# BIAS.net
KiCad netlist of a schematic drawn in Altium Designer
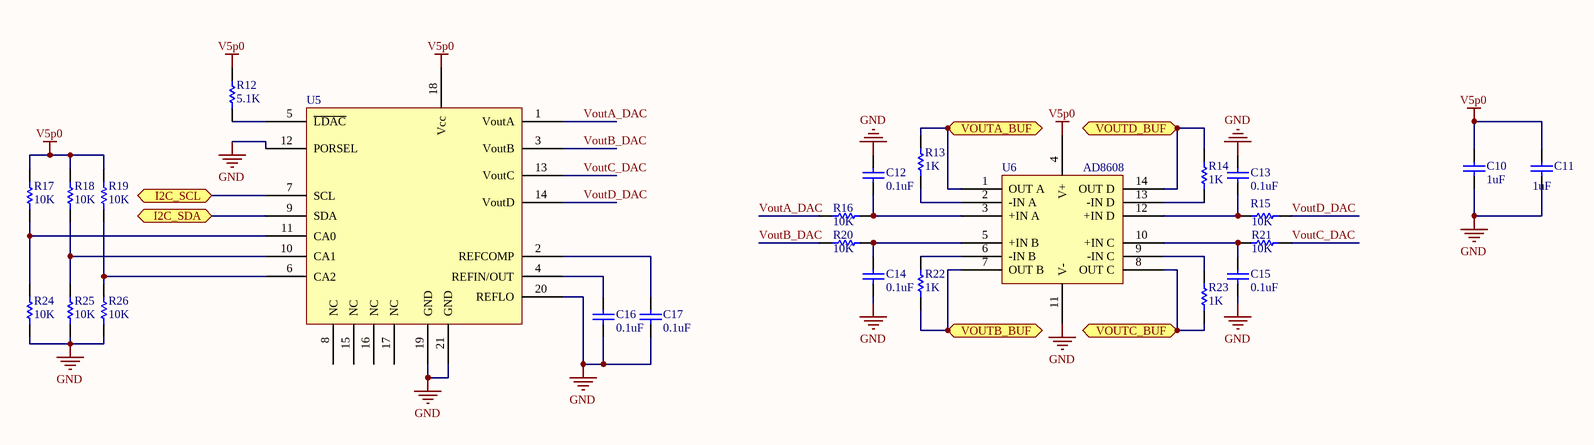
[diagram p0: BIAS.SchDoc]

(export (version "E")
  (design (tool "Eeschema 10.0.6"))
  (components
    (comp (ref "C10")
      (value "1uF")
      (footprint "CAPC01005(0402)22_N")
      (fields (field (name "Comment") "CAP, 0402, 1uF"))
      (libsource (lib "Components") (part "CAP, 0402, 1uF"))
    )
    (comp (ref "C11")
      (value "1uF")
      (footprint "CAPC01005(0402)22_N")
      (fields (field (name "Comment") "CAP, 0402, 1uF"))
      (libsource (lib "Components") (part "CAP, 0402, 1uF"))
    )
    (comp (ref "C12")
      (value "0.1uF")
      (footprint "CAPC01005(0402)22_N")
      (fields (field (name "Comment") "CAP, 0402, 0.1uF"))
      (libsource (lib "Components") (part "CAP, 0402, 0.1uF"))
    )
    (comp (ref "C13")
      (value "0.1uF")
      (footprint "CAPC01005(0402)22_N")
      (fields (field (name "Comment") "CAP, 0402, 0.1uF"))
      (libsource (lib "Components") (part "CAP, 0402, 0.1uF"))
    )
    (comp (ref "C14")
      (value "0.1uF")
      (footprint "CAPC01005(0402)22_N")
      (fields (field (name "Comment") "CAP, 0402, 0.1uF"))
      (libsource (lib "Components") (part "CAP, 0402, 0.1uF"))
    )
    (comp (ref "C15")
      (value "0.1uF")
      (footprint "CAPC01005(0402)22_N")
      (fields (field (name "Comment") "CAP, 0402, 0.1uF"))
      (libsource (lib "Components") (part "CAP, 0402, 0.1uF"))
    )
    (comp (ref "C16")
      (value "0.1uF")
      (footprint "CAPC01005(0402)22_N")
      (fields (field (name "Comment") "CAP, 0402, 0.1uF"))
      (libsource (lib "Components") (part "CAP, 0402, 0.1uF"))
    )
    (comp (ref "C17")
      (value "0.1uF")
      (footprint "CAPC01005(0402)22_N")
      (fields (field (name "Comment") "CAP, 0402, 0.1uF"))
      (libsource (lib "Components") (part "CAP, 0402, 0.1uF"))
    )
    (comp (ref "R12")
      (value "5.1K")
      (footprint "RES, 0603")
      (description "Resistor, 0603, 1/10W, 5.1K ohm")
      (fields
        (field (name "MANUFACTURER") "Panasonic Electronic Components")
        (field (name "MANUFACTURER PART NUMBER") "ERJ-3EKF5101V")
      )
      (libsource (lib "Resistors0603") (part "RES_0603_5.1K"))
    )
    (comp (ref "R13")
      (value "1K")
      (footprint "RES, 0603")
      (description "Resistor, 0603, 1/10W, 1K ohm")
      (fields
        (field (name "MANUFACTURER") "Panasonic Electronic Components")
        (field (name "MANUFACTURER PART NUMBER") "ERJ-3EKF1001V")
      )
      (libsource (lib "Resistors0603") (part "RES_0603_1K"))
    )
    (comp (ref "R14")
      (value "1K")
      (footprint "RES, 0603")
      (description "Resistor, 0603, 1/10W, 1K ohm")
      (fields
        (field (name "MANUFACTURER") "Panasonic Electronic Components")
        (field (name "MANUFACTURER PART NUMBER") "ERJ-3EKF1001V")
      )
      (libsource (lib "Resistors0603") (part "RES_0603_1K"))
    )
    (comp (ref "R15")
      (value "10K")
      (footprint "RES, 0603")
      (description "Resistor, 0603, 1/10W, 10K ohm")
      (fields
        (field (name "MANUFACTURER") "Panasonic Electronic Components")
        (field (name "MANUFACTURER PART NUMBER") "ERJ-3EKF1002V")
      )
      (libsource (lib "Resistors0603") (part "RES_0603_10K"))
    )
    (comp (ref "R16")
      (value "10K")
      (footprint "RES, 0603")
      (description "Resistor, 0603, 1/10W, 10K ohm")
      (fields
        (field (name "MANUFACTURER") "Panasonic Electronic Components")
        (field (name "MANUFACTURER PART NUMBER") "ERJ-3EKF1002V")
      )
      (libsource (lib "Resistors0603") (part "RES_0603_10K"))
    )
    (comp (ref "R17")
      (value "10K")
      (footprint "RES, 0603")
      (description "Resistor, 0603, 1/10W, 10K ohm")
      (fields
        (field (name "MANUFACTURER") "Panasonic Electronic Components")
        (field (name "MANUFACTURER PART NUMBER") "ERJ-3EKF1002V")
      )
      (libsource (lib "Resistors0603") (part "RES_0603_10K"))
    )
    (comp (ref "R18")
      (value "10K")
      (footprint "RES, 0603")
      (description "Resistor, 0603, 1/10W, 10K ohm")
      (fields
        (field (name "MANUFACTURER") "Panasonic Electronic Components")
        (field (name "MANUFACTURER PART NUMBER") "ERJ-3EKF1002V")
      )
      (libsource (lib "Resistors0603") (part "RES_0603_10K"))
    )
    (comp (ref "R19")
      (value "10K")
      (footprint "RES, 0603")
      (description "Resistor, 0603, 1/10W, 10K ohm")
      (fields
        (field (name "MANUFACTURER") "Panasonic Electronic Components")
        (field (name "MANUFACTURER PART NUMBER") "ERJ-3EKF1002V")
      )
      (libsource (lib "Resistors0603") (part "RES_0603_10K"))
    )
    (comp (ref "R20")
      (value "10K")
      (footprint "RES, 0603")
      (description "Resistor, 0603, 1/10W, 10K ohm")
      (fields
        (field (name "MANUFACTURER") "Panasonic Electronic Components")
        (field (name "MANUFACTURER PART NUMBER") "ERJ-3EKF1002V")
      )
      (libsource (lib "Resistors0603") (part "RES_0603_10K"))
    )
    (comp (ref "R21")
      (value "10K")
      (footprint "RES, 0603")
      (description "Resistor, 0603, 1/10W, 10K ohm")
      (fields
        (field (name "MANUFACTURER") "Panasonic Electronic Components")
        (field (name "MANUFACTURER PART NUMBER") "ERJ-3EKF1002V")
      )
      (libsource (lib "Resistors0603") (part "RES_0603_10K"))
    )
    (comp (ref "R22")
      (value "1K")
      (footprint "RES, 0603")
      (description "Resistor, 0603, 1/10W, 1K ohm")
      (fields
        (field (name "MANUFACTURER") "Panasonic Electronic Components")
        (field (name "MANUFACTURER PART NUMBER") "ERJ-3EKF1001V")
      )
      (libsource (lib "Resistors0603") (part "RES_0603_1K"))
    )
    (comp (ref "R23")
      (value "1K")
      (footprint "RES, 0603")
      (description "Resistor, 0603, 1/10W, 1K ohm")
      (fields
        (field (name "MANUFACTURER") "Panasonic Electronic Components")
        (field (name "MANUFACTURER PART NUMBER") "ERJ-3EKF1001V")
      )
      (libsource (lib "Resistors0603") (part "RES_0603_1K"))
    )
    (comp (ref "R24")
      (value "10K")
      (footprint "RES, 0603")
      (description "Resistor, 0603, 1/10W, 10K ohm")
      (fields
        (field (name "MANUFACTURER") "Panasonic Electronic Components")
        (field (name "MANUFACTURER PART NUMBER") "ERJ-3EKF1002V")
      )
      (libsource (lib "Resistors0603") (part "RES_0603_10K"))
    )
    (comp (ref "R25")
      (value "10K")
      (footprint "RES, 0603")
      (description "Resistor, 0603, 1/10W, 10K ohm")
      (fields
        (field (name "MANUFACTURER") "Panasonic Electronic Components")
        (field (name "MANUFACTURER PART NUMBER") "ERJ-3EKF1002V")
      )
      (libsource (lib "Resistors0603") (part "RES_0603_10K"))
    )
    (comp (ref "R26")
      (value "10K")
      (footprint "RES, 0603")
      (description "Resistor, 0603, 1/10W, 10K ohm")
      (fields
        (field (name "MANUFACTURER") "Panasonic Electronic Components")
        (field (name "MANUFACTURER PART NUMBER") "ERJ-3EKF1002V")
      )
      (libsource (lib "Resistors0603") (part "RES_0603_10K"))
    )
    (comp (ref "U5")
      (value "LTC2655")
      (footprint "QFN50P400X400X70-20N")
      (description "Quad I2C 16-/12-Bit Rail-to-Rail DACs with 10ppm/°C Max Reference")
      (libsource (lib "Components") (part "LTC2655"))
    )
    (comp (ref "U6")
      (value "AD8608")
      (footprint "TSOP65P640X120-14N")
      (description "IC OPAMP GP 10MHZ RRO 14SOIC")
      (fields
        (field (name "MANUFACTURER") "Analog Devices Inc")
        (field (name "MANUFACTURER PART NUMBER") "AD8608ARZ-REEL")
      )
      (libsource (lib "Components") (part "AD8608; Quad Op-Amp"))
    )
  )
  (nets
    (net (code "1") (name "/I2C_SCL") (class "Default")
      (node (ref "U5") (pin "7") (pinfunction "SCL_7") (pintype "passive"))
    )
    (net (code "2") (name "/I2C_SDA") (class "Default")
      (node (ref "U5") (pin "9") (pinfunction "SDA_9") (pintype "passive"))
    )
    (net (code "3") (name "/VOUTA_BUF") (class "Default")
      (node (ref "R13") (pin "2") (pinfunction "2_2") (pintype "passive"))
      (node (ref "U6") (pin "1") (pinfunction "OUT_A_1") (pintype "passive"))
    )
    (net (code "4") (name "/VOUTB_BUF") (class "Default")
      (node (ref "R22") (pin "1") (pinfunction "1_1") (pintype "passive"))
      (node (ref "U6") (pin "7") (pinfunction "OUT_B_7") (pintype "passive"))
    )
    (net (code "5") (name "/VOUTC_BUF") (class "Default")
      (node (ref "R23") (pin "2") (pinfunction "2_2") (pintype "passive"))
      (node (ref "U6") (pin "8") (pinfunction "OUT_C_8") (pintype "passive"))
    )
    (net (code "6") (name "/VOUTD_BUF") (class "Default")
      (node (ref "R14") (pin "1") (pinfunction "1_1") (pintype "passive"))
      (node (ref "U6") (pin "14") (pinfunction "OUT_D_14") (pintype "passive"))
    )
    (net (code "7") (name "/VoutA_DAC") (class "Default")
      (node (ref "R16") (pin "1") (pinfunction "1_1") (pintype "passive"))
      (node (ref "U5") (pin "1") (pinfunction "VoutA_1") (pintype "passive"))
    )
    (net (code "8") (name "/VoutB_DAC") (class "Default")
      (node (ref "R20") (pin "1") (pinfunction "1_1") (pintype "passive"))
      (node (ref "U5") (pin "3") (pinfunction "VoutB_3") (pintype "passive"))
    )
    (net (code "9") (name "/VoutC_DAC") (class "Default")
      (node (ref "R21") (pin "1") (pinfunction "1_1") (pintype "passive"))
      (node (ref "U5") (pin "13") (pinfunction "VoutC_13") (pintype "passive"))
    )
    (net (code "10") (name "/VoutD_DAC") (class "Default")
      (node (ref "R15") (pin "1") (pinfunction "1_1") (pintype "passive"))
      (node (ref "U5") (pin "14") (pinfunction "VoutD_14") (pintype "passive"))
    )
    (net (code "11") (name "GND") (class "Default")
      (node (ref "C10") (pin "1") (pinfunction "1_1") (pintype "passive"))
      (node (ref "C11") (pin "1") (pinfunction "1_1") (pintype "passive"))
      (node (ref "C12") (pin "2") (pinfunction "2_2") (pintype "passive"))
      (node (ref "C13") (pin "1") (pinfunction "1_1") (pintype "passive"))
      (node (ref "C14") (pin "1") (pinfunction "1_1") (pintype "passive"))
      (node (ref "C15") (pin "2") (pinfunction "2_2") (pintype "passive"))
      (node (ref "C16") (pin "1") (pinfunction "1_1") (pintype "passive"))
      (node (ref "C17") (pin "1") (pinfunction "1_1") (pintype "passive"))
      (node (ref "R24") (pin "2") (pinfunction "2_2") (pintype "passive"))
      (node (ref "R25") (pin "2") (pinfunction "2_2") (pintype "passive"))
      (node (ref "R26") (pin "2") (pinfunction "2_2") (pintype "passive"))
      (node (ref "U5") (pin "12") (pinfunction "PORSEL_12") (pintype "passive"))
      (node (ref "U5") (pin "19") (pinfunction "GND_19") (pintype "passive"))
      (node (ref "U5") (pin "20") (pinfunction "REFLO_20") (pintype "passive"))
      (node (ref "U5") (pin "21") (pinfunction "GND_21") (pintype "passive"))
      (node (ref "U6") (pin "11") (pinfunction "V-_11") (pintype "passive"))
    )
    (net (code "12") (name "Net-(U5-CA0)") (class "Default")
      (node (ref "R17") (pin "2") (pinfunction "2_2") (pintype "passive"))
      (node (ref "R24") (pin "1") (pinfunction "1_1") (pintype "passive"))
      (node (ref "U5") (pin "11") (pinfunction "CA0_11") (pintype "passive"))
    )
    (net (code "13") (name "Net-(U5-CA1)") (class "Default")
      (node (ref "R18") (pin "2") (pinfunction "2_2") (pintype "passive"))
      (node (ref "R25") (pin "1") (pinfunction "1_1") (pintype "passive"))
      (node (ref "U5") (pin "10") (pinfunction "CA1_10") (pintype "passive"))
    )
    (net (code "14") (name "Net-(U5-CA2)") (class "Default")
      (node (ref "R19") (pin "2") (pinfunction "2_2") (pintype "passive"))
      (node (ref "R26") (pin "1") (pinfunction "1_1") (pintype "passive"))
      (node (ref "U5") (pin "6") (pinfunction "CA2_6") (pintype "passive"))
    )
    (net (code "15") (name "Net-(U5-REFCOMP)") (class "Default")
      (node (ref "C17") (pin "2") (pinfunction "2_2") (pintype "passive"))
      (node (ref "U5") (pin "2") (pinfunction "REFCOMP_2") (pintype "passive"))
    )
    (net (code "16") (name "Net-(U5-REFIN{slash}OUT)") (class "Default")
      (node (ref "C16") (pin "2") (pinfunction "2_2") (pintype "passive"))
      (node (ref "U5") (pin "4") (pinfunction "REFIN/OUT_4") (pintype "passive"))
    )
    (net (code "17") (name "Net-(U5-~{LDAC})") (class "Default")
      (node (ref "R12") (pin "1") (pinfunction "1_1") (pintype "passive"))
      (node (ref "U5") (pin "5") (pinfunction "~{LDAC}_5") (pintype "passive"))
    )
    (net (code "18") (name "Net-(U6-+IN_A)") (class "Default")
      (node (ref "C12") (pin "1") (pinfunction "1_1") (pintype "passive"))
      (node (ref "R16") (pin "2") (pinfunction "2_2") (pintype "passive"))
      (node (ref "U6") (pin "3") (pinfunction "+IN_A_3") (pintype "passive"))
    )
    (net (code "19") (name "Net-(U6-+IN_B)") (class "Default")
      (node (ref "C14") (pin "2") (pinfunction "2_2") (pintype "passive"))
      (node (ref "R20") (pin "2") (pinfunction "2_2") (pintype "passive"))
      (node (ref "U6") (pin "5") (pinfunction "+IN_B_5") (pintype "passive"))
    )
    (net (code "20") (name "Net-(U6-+IN_C)") (class "Default")
      (node (ref "C15") (pin "1") (pinfunction "1_1") (pintype "passive"))
      (node (ref "R21") (pin "2") (pinfunction "2_2") (pintype "passive"))
      (node (ref "U6") (pin "10") (pinfunction "+IN_C_10") (pintype "passive"))
    )
    (net (code "21") (name "Net-(U6-+IN_D)") (class "Default")
      (node (ref "C13") (pin "2") (pinfunction "2_2") (pintype "passive"))
      (node (ref "R15") (pin "2") (pinfunction "2_2") (pintype "passive"))
      (node (ref "U6") (pin "12") (pinfunction "+IN_D_12") (pintype "passive"))
    )
    (net (code "22") (name "Net-(U6--IN_A)") (class "Default")
      (node (ref "R13") (pin "1") (pinfunction "1_1") (pintype "passive"))
      (node (ref "U6") (pin "2") (pinfunction "-IN_A_2") (pintype "passive"))
    )
    (net (code "23") (name "Net-(U6--IN_B)") (class "Default")
      (node (ref "R22") (pin "2") (pinfunction "2_2") (pintype "passive"))
      (node (ref "U6") (pin "6") (pinfunction "-IN_B_6") (pintype "passive"))
    )
    (net (code "24") (name "Net-(U6--IN_C)") (class "Default")
      (node (ref "R23") (pin "1") (pinfunction "1_1") (pintype "passive"))
      (node (ref "U6") (pin "9") (pinfunction "-IN_C_9") (pintype "passive"))
    )
    (net (code "25") (name "Net-(U6--IN_D)") (class "Default")
      (node (ref "R14") (pin "2") (pinfunction "2_2") (pintype "passive"))
      (node (ref "U6") (pin "13") (pinfunction "-IN_D_13") (pintype "passive"))
    )
    (net (code "26") (name "V5p0") (class "Default")
      (node (ref "C10") (pin "2") (pinfunction "2_2") (pintype "passive"))
      (node (ref "C11") (pin "2") (pinfunction "2_2") (pintype "passive"))
      (node (ref "R12") (pin "2") (pinfunction "2_2") (pintype "passive"))
      (node (ref "R17") (pin "1") (pinfunction "1_1") (pintype "passive"))
      (node (ref "R18") (pin "1") (pinfunction "1_1") (pintype "passive"))
      (node (ref "R19") (pin "1") (pinfunction "1_1") (pintype "passive"))
      (node (ref "U5") (pin "18") (pinfunction "Vcc_18") (pintype "passive"))
      (node (ref "U6") (pin "4") (pinfunction "V+_4") (pintype "passive"))
    )
    (net (code "27") (name "unconnected-(U5-NC-Pad8)") (class "Default")
      (node (ref "U5") (pin "8") (pinfunction "NC_8") (pintype "passive"))
    )
    (net (code "28") (name "unconnected-(U5-NC-Pad15)") (class "Default")
      (node (ref "U5") (pin "15") (pinfunction "NC_15") (pintype "passive"))
    )
    (net (code "29") (name "unconnected-(U5-NC-Pad16)") (class "Default")
      (node (ref "U5") (pin "16") (pinfunction "NC_16") (pintype "passive"))
    )
    (net (code "30") (name "unconnected-(U5-NC-Pad17)") (class "Default")
      (node (ref "U5") (pin "17") (pinfunction "NC_17") (pintype "passive"))
    )
  )
)
